# Remote_Control_Wiring.net
KiCad netlist of a schematic drawn in EAGLE
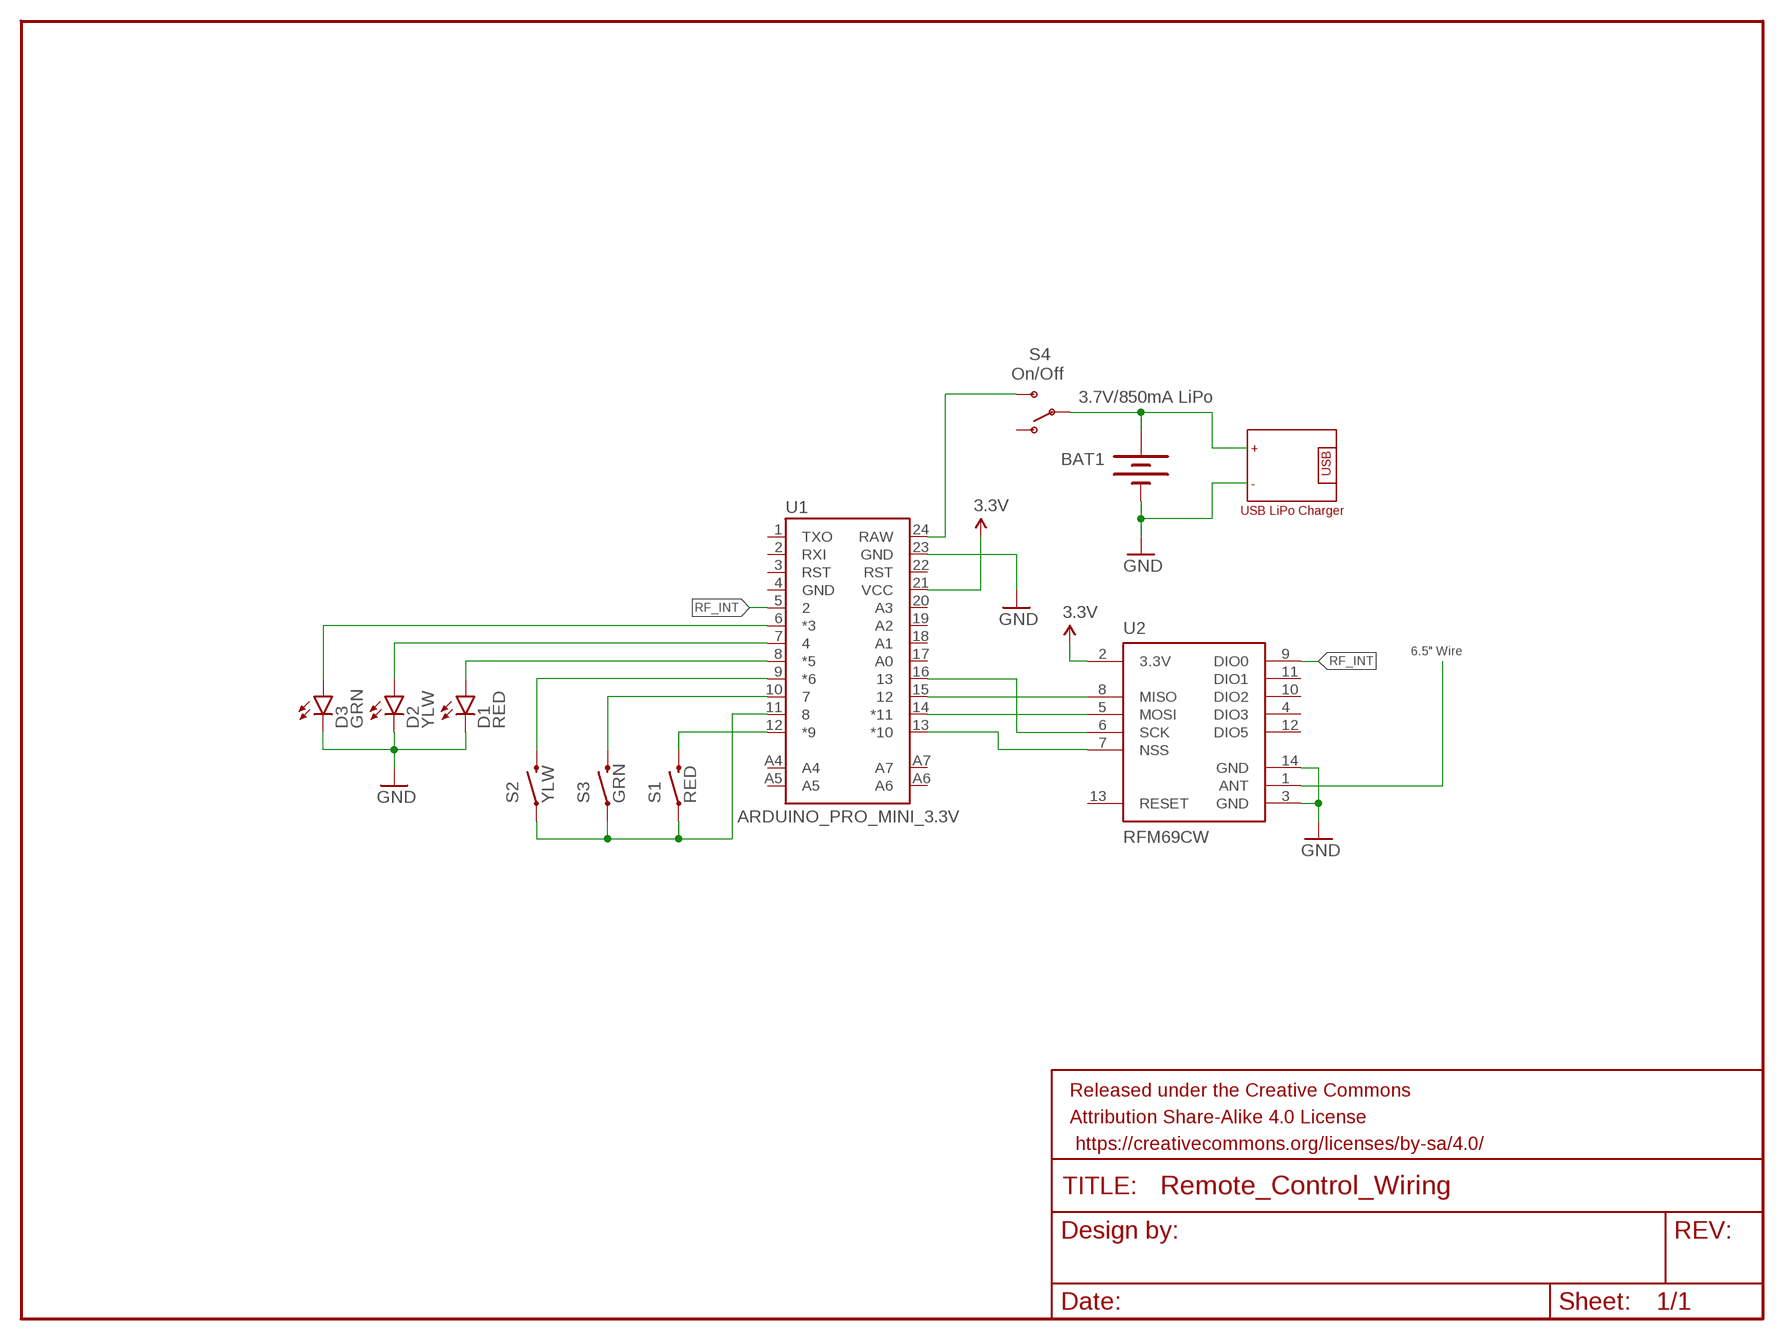
[diagram p0: schematic, sheet 1]

(export (version "E")
  (design (tool "Eeschema 10.0.6"))
  (components
    (comp (ref "BAT1")
      (value "3.7V/850mA LiPo")
      (footprint "eagle-import:LIPO-110-TABS")
      (libsource (lib "eagle-import") (part "BATTERYLIPO-TABS"))
    )
    (comp (ref "D1")
      (value "RED")
      (footprint "eagle-import:LED5MM")
      (libsource (lib "eagle-import") (part "LED5MM"))
    )
    (comp (ref "D2")
      (value "YLW")
      (footprint "eagle-import:LED5MM")
      (libsource (lib "eagle-import") (part "LED5MM"))
    )
    (comp (ref "D3")
      (value "GRN")
      (footprint "eagle-import:LED5MM")
      (libsource (lib "eagle-import") (part "LED5MM"))
    )
    (comp (ref "FRAME1")
      (value "FRAME-LETTER")
      (footprint "eagle-import:CREATIVE_COMMONS")
      (libsource (lib "eagle-import") (part "FRAME-LETTER"))
    )
    (comp (ref "S1")
      (value "RED")
      (footprint "eagle-import:TACTILE-PTH")
      (libsource (lib "eagle-import") (part "SWITCH-MOMENTARY-2PTH"))
    )
    (comp (ref "S2")
      (value "YLW")
      (footprint "eagle-import:TACTILE-PTH")
      (libsource (lib "eagle-import") (part "SWITCH-MOMENTARY-2PTH"))
    )
    (comp (ref "S3")
      (value "GRN")
      (footprint "eagle-import:TACTILE-PTH")
      (libsource (lib "eagle-import") (part "SWITCH-MOMENTARY-2PTH"))
    )
    (comp (ref "S4")
      (value "On/Off")
      (footprint "eagle-import:SWITCH-SPDT")
      (libsource (lib "eagle-import") (part "SWITCH-SPDTPTH"))
    )
    (comp (ref "U1")
      (value "ARDUINO_PRO_MINI_3.3V")
      (footprint "eagle-import:ARDUINO_PRO_MINI")
      (libsource (lib "eagle-import") (part "ARDUINO_PRO_MINI"))
    )
    (comp (ref "U2")
      (value "RFM69CW")
      (footprint "eagle-import:RFM69CW-XXXS2")
      (libsource (lib "eagle-import") (part "RFM69CW"))
    )
  )
  (nets
    (net (code "1") (name "3.3V") (class "Default")
      (node (ref "U1") (pin "21") (pinfunction "VCC_21") (pintype "bidirectional"))
      (node (ref "U2") (pin "2") (pinfunction "3.3V_2") (pintype "power_in"))
    )
    (net (code "2") (name "GND") (class "Default")
      (node (ref "BAT1") (pin "-") (pinfunction "-_-") (pintype "power_in"))
      (node (ref "D1") (pin "K") (pinfunction "C_K") (pintype "passive"))
      (node (ref "D2") (pin "K") (pinfunction "C_K") (pintype "passive"))
      (node (ref "D3") (pin "K") (pinfunction "C_K") (pintype "passive"))
      (node (ref "U1") (pin "23") (pinfunction "GND_23") (pintype "bidirectional"))
      (node (ref "U2") (pin "14") (pinfunction "GND_14") (pintype "power_in"))
      (node (ref "U2") (pin "3") (pinfunction "GND_3") (pintype "power_in"))
    )
    (net (code "3") (name "Net-(S1-2)") (class "Default")
      (node (ref "S1") (pin "3") (pinfunction "2_3") (pintype "passive"))
      (node (ref "U1") (pin "12") (pinfunction "*9_12") (pintype "bidirectional"))
    )
    (net (code "4") (name "Net-(S2-2)") (class "Default")
      (node (ref "S2") (pin "3") (pinfunction "2_3") (pintype "passive"))
      (node (ref "U1") (pin "9") (pinfunction "*6_9") (pintype "bidirectional"))
    )
    (net (code "5") (name "Net-(S3-2)") (class "Default")
      (node (ref "S3") (pin "3") (pinfunction "2_3") (pintype "passive"))
      (node (ref "U1") (pin "10") (pinfunction "7_10") (pintype "bidirectional"))
    )
    (net (code "6") (name "Net-(S4-P)") (class "Default")
      (node (ref "BAT1") (pin "+") (pinfunction "+_+") (pintype "power_in"))
      (node (ref "S4") (pin "2") (pinfunction "P_2") (pintype "passive"))
    )
    (net (code "7") (name "Net-(S4-S)") (class "Default")
      (node (ref "S4") (pin "3") (pinfunction "S_3") (pintype "passive"))
      (node (ref "U1") (pin "24") (pinfunction "RAW_24") (pintype "bidirectional"))
    )
    (net (code "8") (name "Net-(U1-*3)") (class "Default")
      (node (ref "D3") (pin "A") (pinfunction "A_A") (pintype "passive"))
      (node (ref "U1") (pin "6") (pinfunction "*3_6") (pintype "bidirectional"))
    )
    (net (code "9") (name "Net-(U1-*5)") (class "Default")
      (node (ref "D1") (pin "A") (pinfunction "A_A") (pintype "passive"))
      (node (ref "U1") (pin "8") (pinfunction "*5_8") (pintype "bidirectional"))
    )
    (net (code "10") (name "Net-(U1-*10)") (class "Default")
      (node (ref "U1") (pin "13") (pinfunction "*10_13") (pintype "bidirectional"))
      (node (ref "U2") (pin "7") (pinfunction "NSS_7") (pintype "input"))
    )
    (net (code "11") (name "Net-(U1-*11)") (class "Default")
      (node (ref "U1") (pin "14") (pinfunction "*11_14") (pintype "bidirectional"))
      (node (ref "U2") (pin "5") (pinfunction "MOSI_5") (pintype "input"))
    )
    (net (code "12") (name "Net-(U1-4)") (class "Default")
      (node (ref "D2") (pin "A") (pinfunction "A_A") (pintype "passive"))
      (node (ref "U1") (pin "7") (pinfunction "4_7") (pintype "bidirectional"))
    )
    (net (code "13") (name "Net-(U1-8)") (class "Default")
      (node (ref "S1") (pin "1") (pinfunction "1_1") (pintype "passive"))
      (node (ref "S2") (pin "1") (pinfunction "1_1") (pintype "passive"))
      (node (ref "S3") (pin "1") (pinfunction "1_1") (pintype "passive"))
      (node (ref "U1") (pin "11") (pinfunction "8_11") (pintype "bidirectional"))
    )
    (net (code "14") (name "Net-(U1-12)") (class "Default")
      (node (ref "U1") (pin "15") (pinfunction "12_15") (pintype "bidirectional"))
      (node (ref "U2") (pin "8") (pinfunction "MISO_8") (pintype "bidirectional"))
    )
    (net (code "15") (name "Net-(U1-13)") (class "Default")
      (node (ref "U1") (pin "16") (pinfunction "13_16") (pintype "bidirectional"))
      (node (ref "U2") (pin "6") (pinfunction "SCK_6") (pintype "input"))
    )
    (net (code "16") (name "RF_INT") (class "Default")
      (node (ref "U1") (pin "5") (pinfunction "2_5") (pintype "bidirectional"))
      (node (ref "U2") (pin "9") (pinfunction "DIO0_9") (pintype "bidirectional"))
    )
    (net (code "17") (name "unconnected-(S4-O-Pad1)") (class "Default")
      (node (ref "S4") (pin "1") (pinfunction "O_1") (pintype "passive"))
    )
    (net (code "18") (name "unconnected-(U1-A0-Pad17)") (class "Default")
      (node (ref "U1") (pin "17") (pinfunction "A0_17") (pintype "bidirectional"))
    )
    (net (code "19") (name "unconnected-(U1-A1-Pad18)") (class "Default")
      (node (ref "U1") (pin "18") (pinfunction "A1_18") (pintype "bidirectional"))
    )
    (net (code "20") (name "unconnected-(U1-A2-Pad19)") (class "Default")
      (node (ref "U1") (pin "19") (pinfunction "A2_19") (pintype "bidirectional"))
    )
    (net (code "21") (name "unconnected-(U1-A3-Pad20)") (class "Default")
      (node (ref "U1") (pin "20") (pinfunction "A3_20") (pintype "bidirectional"))
    )
    (net (code "22") (name "unconnected-(U1-GND-Pad4)") (class "Default")
      (node (ref "U1") (pin "4") (pinfunction "GND_4") (pintype "bidirectional"))
    )
    (net (code "23") (name "unconnected-(U1-PadA4)") (class "Default")
      (node (ref "U1") (pin "A4") (pinfunction "A4_A4") (pintype "bidirectional"))
    )
    (net (code "24") (name "unconnected-(U1-PadA5)") (class "Default")
      (node (ref "U1") (pin "A5") (pinfunction "A5_A5") (pintype "bidirectional"))
    )
    (net (code "25") (name "unconnected-(U1-PadA6)") (class "Default")
      (node (ref "U1") (pin "A6") (pinfunction "A6_A6") (pintype "bidirectional"))
    )
    (net (code "26") (name "unconnected-(U1-PadA7)") (class "Default")
      (node (ref "U1") (pin "A7") (pinfunction "A7_A7") (pintype "bidirectional"))
    )
    (net (code "27") (name "unconnected-(U1-RST-Pad3)") (class "Default")
      (node (ref "U1") (pin "3") (pinfunction "RST_3") (pintype "bidirectional"))
    )
    (net (code "28") (name "unconnected-(U1-RST-Pad22)") (class "Default")
      (node (ref "U1") (pin "22") (pinfunction "RST_22") (pintype "bidirectional"))
    )
    (net (code "29") (name "unconnected-(U1-RXI-Pad2)") (class "Default")
      (node (ref "U1") (pin "2") (pinfunction "RXI_2") (pintype "bidirectional"))
    )
    (net (code "30") (name "unconnected-(U1-TXO-Pad1)") (class "Default")
      (node (ref "U1") (pin "1") (pinfunction "TXO_1") (pintype "bidirectional"))
    )
    (net (code "31") (name "unconnected-(U2-ANT-Pad1)") (class "Default")
      (node (ref "U2") (pin "1") (pinfunction "ANT_1") (pintype "passive"))
    )
    (net (code "32") (name "unconnected-(U2-DIO1-Pad11)") (class "Default")
      (node (ref "U2") (pin "11") (pinfunction "DIO1_11") (pintype "bidirectional"))
    )
    (net (code "33") (name "unconnected-(U2-DIO2-Pad10)") (class "Default")
      (node (ref "U2") (pin "10") (pinfunction "DIO2_10") (pintype "bidirectional"))
    )
    (net (code "34") (name "unconnected-(U2-DIO3-Pad4)") (class "Default")
      (node (ref "U2") (pin "4") (pinfunction "DIO3_4") (pintype "bidirectional"))
    )
    (net (code "35") (name "unconnected-(U2-DIO5-Pad12)") (class "Default")
      (node (ref "U2") (pin "12") (pinfunction "DIO5_12") (pintype "bidirectional"))
    )
    (net (code "36") (name "unconnected-(U2-RESET-Pad13)") (class "Default")
      (node (ref "U2") (pin "13") (pinfunction "RESET_13") (pintype "input"))
    )
  )
)
